# capacitive_sensor_V1.net
KiCad netlist of a schematic drawn in EAGLE
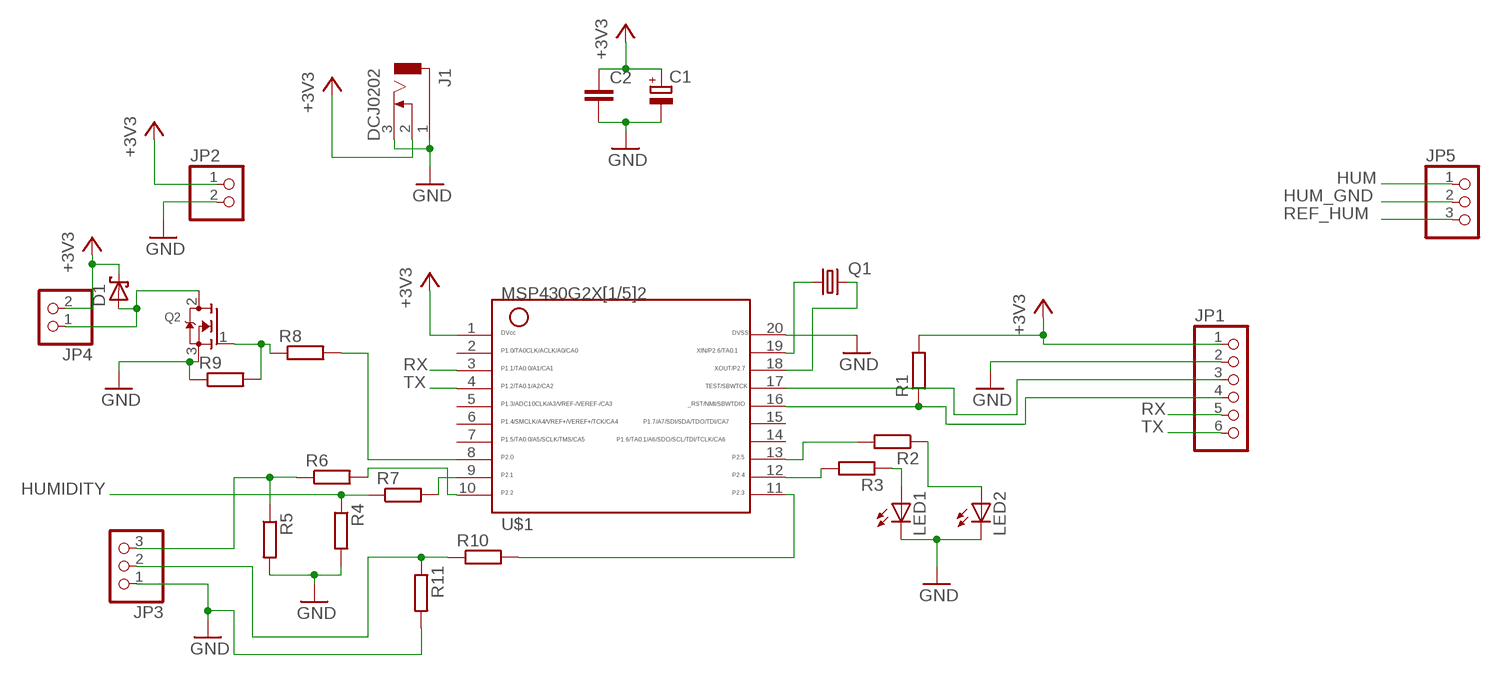
[diagram p0: schematic, sheet 1]

(export (version "E")
  (design (tool "Eeschema 10.0.6"))
  (components
    (comp (ref "C1")
      (value "CPOL-EUE5-8.5")
      (footprint "eagle-import:E5-8,5")
      (libsource (lib "eagle-import") (part "CPOL-EUE5-8.5"))
    )
    (comp (ref "C2")
      (value "C-EU025-030X050")
      (footprint "eagle-import:C025-030X050")
      (libsource (lib "eagle-import") (part "C-EU025-030X050"))
    )
    (comp (ref "D1")
      (value "SCHOTTKY-DIODEDO41-7")
      (footprint "eagle-import:DO41-7")
      (libsource (lib "eagle-import") (part "SCHOTTKY-DIODEDO41-7"))
    )
    (comp (ref "J1")
      (value "DCJ0202")
      (footprint "eagle-import:DCJ0202")
      (libsource (lib "eagle-import") (part "DCJ0202"))
    )
    (comp (ref "JP1")
      (value "HEADER-1X6")
      (footprint "eagle-import:1X06_OVAL")
      (libsource (lib "eagle-import") (part "HEADER-1X6"))
    )
    (comp (ref "JP2")
      (value "HEADER-1X2")
      (footprint "eagle-import:1X02_OVAL")
      (libsource (lib "eagle-import") (part "HEADER-1X2"))
    )
    (comp (ref "JP3")
      (value "PINHD-1X3")
      (footprint "eagle-import:1X03")
      (libsource (lib "eagle-import") (part "PINHD-1X3"))
    )
    (comp (ref "JP4")
      (value "HEADER-1X2")
      (footprint "eagle-import:1X02_OVAL")
      (libsource (lib "eagle-import") (part "HEADER-1X2"))
    )
    (comp (ref "JP5")
      (value "PINHD-1X3")
      (footprint "eagle-import:1X03")
      (libsource (lib "eagle-import") (part "PINHD-1X3"))
    )
    (comp (ref "LED1")
      (value "LED3MM")
      (footprint "eagle-import:LED3MM")
      (libsource (lib "eagle-import") (part "LED3MM"))
    )
    (comp (ref "LED2")
      (value "LED3MM")
      (footprint "eagle-import:LED3MM")
      (libsource (lib "eagle-import") (part "LED3MM"))
    )
    (comp (ref "Q1")
      (value "CRYSTALTC26H")
      (footprint "eagle-import:TC26H")
      (libsource (lib "eagle-import") (part "CRYSTALTC26H"))
    )
    (comp (ref "Q2")
      (value "MOSFET-NGDS_TO220V")
      (footprint "eagle-import:TO220V")
      (libsource (lib "eagle-import") (part "MOSFET-NGDS_TO220V"))
    )
    (comp (ref "R1")
      (value "R-EU_0204/7")
      (footprint "eagle-import:0204_7")
      (libsource (lib "eagle-import") (part "R-EU_0204/7"))
    )
    (comp (ref "R2")
      (value "R-EU_0204/7")
      (footprint "eagle-import:0204_7")
      (libsource (lib "eagle-import") (part "R-EU_0204/7"))
    )
    (comp (ref "R3")
      (value "R-EU_0204/7")
      (footprint "eagle-import:0204_7")
      (libsource (lib "eagle-import") (part "R-EU_0204/7"))
    )
    (comp (ref "R4")
      (value "R-EU_0204/7")
      (footprint "eagle-import:0204_7")
      (libsource (lib "eagle-import") (part "R-EU_0204/7"))
    )
    (comp (ref "R5")
      (value "R-EU_0204/7")
      (footprint "eagle-import:0204_7")
      (libsource (lib "eagle-import") (part "R-EU_0204/7"))
    )
    (comp (ref "R6")
      (value "R-EU_0204/7")
      (footprint "eagle-import:0204_7")
      (libsource (lib "eagle-import") (part "R-EU_0204/7"))
    )
    (comp (ref "R7")
      (value "R-EU_0204/7")
      (footprint "eagle-import:0204_7")
      (libsource (lib "eagle-import") (part "R-EU_0204/7"))
    )
    (comp (ref "R8")
      (value "R-EU_0204/7")
      (footprint "eagle-import:0204_7")
      (libsource (lib "eagle-import") (part "R-EU_0204/7"))
    )
    (comp (ref "R9")
      (value "R-EU_0204/7")
      (footprint "eagle-import:0204_7")
      (libsource (lib "eagle-import") (part "R-EU_0204/7"))
    )
    (comp (ref "R10")
      (value "R-EU_0204/7")
      (footprint "eagle-import:0204_7")
      (libsource (lib "eagle-import") (part "R-EU_0204/7"))
    )
    (comp (ref "R11")
      (value "R-EU_0204/7")
      (footprint "eagle-import:0204_7")
      (libsource (lib "eagle-import") (part "R-EU_0204/7"))
    )
    (comp (ref "U$1")
      (value "G2X[1/5]2---N20")
      (footprint "eagle-import:N20")
      (libsource (lib "eagle-import") (part "G2X[1/5]2---N20"))
    )
  )
  (nets
    (net (code "1") (name "+3V3") (class "Default")
      (node (ref "C1") (pin "+") (pinfunction "+_+") (pintype "passive"))
      (node (ref "C2") (pin "1") (pinfunction "1_1") (pintype "passive"))
      (node (ref "D1") (pin "C") (pinfunction "C_C") (pintype "passive"))
      (node (ref "J1") (pin "2") (pinfunction "2_2") (pintype "passive"))
      (node (ref "JP1") (pin "1") (pinfunction "1_1") (pintype "passive"))
      (node (ref "JP2") (pin "1") (pinfunction "1_1") (pintype "passive"))
      (node (ref "JP4") (pin "2") (pinfunction "2_2") (pintype "passive"))
      (node (ref "R1") (pin "2") (pinfunction "2_2") (pintype "passive"))
      (node (ref "U$1") (pin "1") (pinfunction "1_1") (pintype "bidirectional"))
    )
    (net (code "2") (name "/HUM") (class "Default")
      (node (ref "JP5") (pin "1") (pinfunction "1_1") (pintype "passive"))
    )
    (net (code "3") (name "/HUMIDITY") (class "Default")
      (node (ref "R4") (pin "1") (pinfunction "1_1") (pintype "passive"))
      (node (ref "R7") (pin "1") (pinfunction "1_1") (pintype "passive"))
    )
    (net (code "4") (name "/HUM_GND") (class "Default")
      (node (ref "JP5") (pin "2") (pinfunction "2_2") (pintype "passive"))
    )
    (net (code "5") (name "/REF_HUM") (class "Default")
      (node (ref "JP5") (pin "3") (pinfunction "3_3") (pintype "passive"))
    )
    (net (code "6") (name "/RX") (class "Default")
      (node (ref "JP1") (pin "5") (pinfunction "5_5") (pintype "passive"))
      (node (ref "U$1") (pin "3") (pinfunction "3_3") (pintype "bidirectional"))
    )
    (net (code "7") (name "/TX") (class "Default")
      (node (ref "JP1") (pin "6") (pinfunction "6_6") (pintype "passive"))
      (node (ref "U$1") (pin "4") (pinfunction "4_4") (pintype "bidirectional"))
    )
    (net (code "8") (name "GND") (class "Default")
      (node (ref "C1") (pin "-") (pinfunction "-_-") (pintype "passive"))
      (node (ref "C2") (pin "2") (pinfunction "2_2") (pintype "passive"))
      (node (ref "J1") (pin "1") (pinfunction "1_1") (pintype "passive"))
      (node (ref "J1") (pin "3") (pinfunction "3_3") (pintype "passive"))
      (node (ref "JP1") (pin "2") (pinfunction "2_2") (pintype "passive"))
      (node (ref "JP2") (pin "2") (pinfunction "2_2") (pintype "passive"))
      (node (ref "JP3") (pin "1") (pinfunction "1_1") (pintype "passive"))
      (node (ref "LED1") (pin "K") (pinfunction "C_K") (pintype "passive"))
      (node (ref "LED2") (pin "K") (pinfunction "C_K") (pintype "passive"))
      (node (ref "Q2") (pin "3") (pinfunction "S_3") (pintype "bidirectional"))
      (node (ref "R11") (pin "2") (pinfunction "2_2") (pintype "passive"))
      (node (ref "R4") (pin "2") (pinfunction "2_2") (pintype "passive"))
      (node (ref "R5") (pin "2") (pinfunction "2_2") (pintype "passive"))
      (node (ref "R9") (pin "1") (pinfunction "1_1") (pintype "passive"))
      (node (ref "U$1") (pin "20") (pinfunction "20_20") (pintype "bidirectional"))
    )
    (net (code "9") (name "Net-(JP1-Pad3)") (class "Default")
      (node (ref "JP1") (pin "3") (pinfunction "3_3") (pintype "passive"))
      (node (ref "U$1") (pin "17") (pinfunction "17_17") (pintype "bidirectional"))
    )
    (net (code "10") (name "Net-(JP1-Pad4)") (class "Default")
      (node (ref "JP1") (pin "4") (pinfunction "4_4") (pintype "passive"))
      (node (ref "R1") (pin "1") (pinfunction "1_1") (pintype "passive"))
      (node (ref "U$1") (pin "16") (pinfunction "16_16") (pintype "bidirectional"))
    )
    (net (code "11") (name "Net-(JP3-Pad2)") (class "Default")
      (node (ref "JP3") (pin "2") (pinfunction "2_2") (pintype "passive"))
      (node (ref "R10") (pin "1") (pinfunction "1_1") (pintype "passive"))
      (node (ref "R11") (pin "1") (pinfunction "1_1") (pintype "passive"))
    )
    (net (code "12") (name "Net-(JP3-Pad3)") (class "Default")
      (node (ref "JP3") (pin "3") (pinfunction "3_3") (pintype "passive"))
      (node (ref "R5") (pin "1") (pinfunction "1_1") (pintype "passive"))
      (node (ref "R6") (pin "1") (pinfunction "1_1") (pintype "passive"))
    )
    (net (code "13") (name "Net-(LED1-PadA)") (class "Default")
      (node (ref "LED1") (pin "A") (pinfunction "A_A") (pintype "passive"))
      (node (ref "R3") (pin "1") (pinfunction "1_1") (pintype "passive"))
    )
    (net (code "14") (name "Net-(LED2-PadA)") (class "Default")
      (node (ref "LED2") (pin "A") (pinfunction "A_A") (pintype "passive"))
      (node (ref "R2") (pin "1") (pinfunction "1_1") (pintype "passive"))
    )
    (net (code "15") (name "Net-(Q1-Pad1)") (class "Default")
      (node (ref "Q1") (pin "1") (pinfunction "1_1") (pintype "passive"))
      (node (ref "U$1") (pin "19") (pinfunction "19_19") (pintype "bidirectional"))
    )
    (net (code "16") (name "Net-(Q1-Pad2)") (class "Default")
      (node (ref "Q1") (pin "2") (pinfunction "2_2") (pintype "passive"))
      (node (ref "U$1") (pin "18") (pinfunction "18_18") (pintype "bidirectional"))
    )
    (net (code "17") (name "Net-(Q2-D)") (class "Default")
      (node (ref "D1") (pin "A") (pinfunction "A_A") (pintype "passive"))
      (node (ref "JP4") (pin "1") (pinfunction "1_1") (pintype "passive"))
      (node (ref "Q2") (pin "2") (pinfunction "D_2") (pintype "bidirectional"))
    )
    (net (code "18") (name "Net-(Q2-G)") (class "Default")
      (node (ref "Q2") (pin "1") (pinfunction "G_1") (pintype "bidirectional"))
      (node (ref "R8") (pin "1") (pinfunction "1_1") (pintype "passive"))
      (node (ref "R9") (pin "2") (pinfunction "2_2") (pintype "passive"))
    )
    (net (code "19") (name "Net-(R2-Pad2)") (class "Default")
      (node (ref "R2") (pin "2") (pinfunction "2_2") (pintype "passive"))
      (node (ref "U$1") (pin "13") (pinfunction "13_13") (pintype "bidirectional"))
    )
    (net (code "20") (name "Net-(R3-Pad2)") (class "Default")
      (node (ref "R3") (pin "2") (pinfunction "2_2") (pintype "passive"))
      (node (ref "U$1") (pin "12") (pinfunction "12_12") (pintype "bidirectional"))
    )
    (net (code "21") (name "Net-(R6-Pad2)") (class "Default")
      (node (ref "R6") (pin "2") (pinfunction "2_2") (pintype "passive"))
      (node (ref "U$1") (pin "10") (pinfunction "10_10") (pintype "bidirectional"))
    )
    (net (code "22") (name "Net-(R7-Pad2)") (class "Default")
      (node (ref "R7") (pin "2") (pinfunction "2_2") (pintype "passive"))
      (node (ref "U$1") (pin "9") (pinfunction "9_9") (pintype "bidirectional"))
    )
    (net (code "23") (name "Net-(R8-Pad2)") (class "Default")
      (node (ref "R8") (pin "2") (pinfunction "2_2") (pintype "passive"))
      (node (ref "U$1") (pin "8") (pinfunction "8_8") (pintype "bidirectional"))
    )
    (net (code "24") (name "Net-(R10-Pad2)") (class "Default")
      (node (ref "R10") (pin "2") (pinfunction "2_2") (pintype "passive"))
      (node (ref "U$1") (pin "11") (pinfunction "11_11") (pintype "bidirectional"))
    )
    (net (code "25") (name "unconnected-(U$1-Pad2)") (class "Default")
      (node (ref "U$1") (pin "2") (pinfunction "2_2") (pintype "bidirectional"))
    )
    (net (code "26") (name "unconnected-(U$1-Pad5)") (class "Default")
      (node (ref "U$1") (pin "5") (pinfunction "5_5") (pintype "bidirectional"))
    )
    (net (code "27") (name "unconnected-(U$1-Pad6)") (class "Default")
      (node (ref "U$1") (pin "6") (pinfunction "6_6") (pintype "bidirectional"))
    )
    (net (code "28") (name "unconnected-(U$1-Pad7)") (class "Default")
      (node (ref "U$1") (pin "7") (pinfunction "7_7") (pintype "bidirectional"))
    )
    (net (code "29") (name "unconnected-(U$1-Pad14)") (class "Default")
      (node (ref "U$1") (pin "14") (pinfunction "14_14") (pintype "bidirectional"))
    )
    (net (code "30") (name "unconnected-(U$1-Pad15)") (class "Default")
      (node (ref "U$1") (pin "15") (pinfunction "15_15") (pintype "bidirectional"))
    )
  )
)
